# Peripheral.net
KiCad netlist of a schematic drawn in Altium Designer
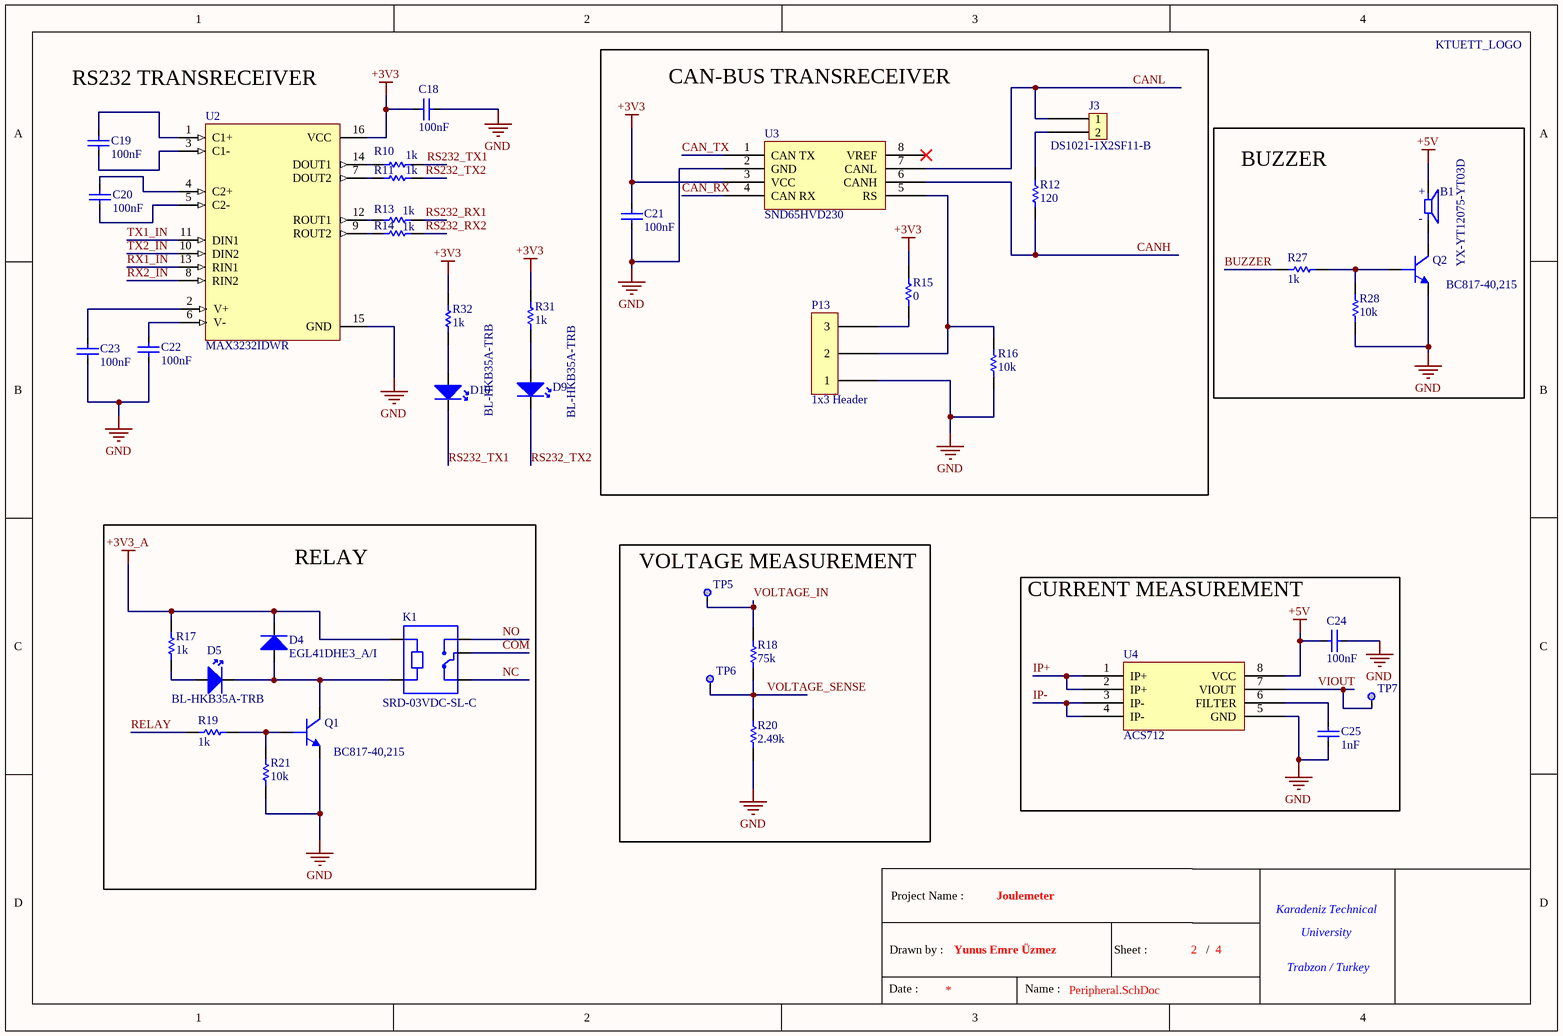
[diagram p0: Peripheral.SchDoc]

(export (version "E")
  (design (tool "Eeschema 10.0.6"))
  (components
    (comp (ref "1")
      (value "KTUETT_LOGO")
      (footprint "KTUETT_LOGO")
      (libsource (lib "Motor_Driver") (part "KTUETT_LOGO"))
    )
    (comp (ref "B1")
      (value "YX-YT12075-YT03D")
      (footprint "BUZZER")
      (fields (field (name "VOLTAGE") "3V") (field (name "MANUFACTURER") "YXDZ"))
      (libsource (lib "jl_lib") (part "YX-YT12075-YT03D"))
    )
    (comp (ref "C18")
      (value "100nF")
      (footprint "CAP-0603")
      (fields
        (field (name "MANUFACTURER") "TDK")
        (field (name "VOLTAGE") "50V")
        (field (name "TOLERANCE") "%10")
      )
      (libsource (lib "Motor_Driver") (part "CGA3E2X7R1H104K080AA"))
    )
    (comp (ref "C19")
      (value "100nF")
      (footprint "CAP-0603")
      (fields
        (field (name "MANUFACTURER") "TDK")
        (field (name "VOLTAGE") "50V")
        (field (name "TOLERANCE") "%10")
      )
      (libsource (lib "Motor_Driver") (part "CGA3E2X7R1H104K080AA"))
    )
    (comp (ref "C20")
      (value "100nF")
      (footprint "CAP-0603")
      (fields
        (field (name "MANUFACTURER") "TDK")
        (field (name "VOLTAGE") "50V")
        (field (name "TOLERANCE") "%10")
      )
      (libsource (lib "Motor_Driver") (part "CGA3E2X7R1H104K080AA"))
    )
    (comp (ref "C21")
      (value "100nF")
      (footprint "CAP-0603")
      (fields
        (field (name "MANUFACTURER") "TDK")
        (field (name "VOLTAGE") "50V")
        (field (name "TOLERANCE") "%10")
      )
      (libsource (lib "Motor_Driver") (part "CGA3E2X7R1H104K080AA"))
    )
    (comp (ref "C22")
      (value "100nF")
      (footprint "CAP-0603")
      (fields
        (field (name "MANUFACTURER") "TDK")
        (field (name "VOLTAGE") "50V")
        (field (name "TOLERANCE") "%10")
      )
      (libsource (lib "Motor_Driver") (part "CGA3E2X7R1H104K080AA"))
    )
    (comp (ref "C23")
      (value "100nF")
      (footprint "CAP-0603")
      (fields
        (field (name "MANUFACTURER") "TDK")
        (field (name "VOLTAGE") "50V")
        (field (name "TOLERANCE") "%10")
      )
      (libsource (lib "Motor_Driver") (part "CGA3E2X7R1H104K080AA"))
    )
    (comp (ref "C24")
      (value "100nF")
      (footprint "CAP-0603")
      (fields
        (field (name "MANUFACTURER") "TDK")
        (field (name "VOLTAGE") "50V")
        (field (name "TOLERANCE") "%10")
      )
      (libsource (lib "Motor_Driver") (part "CGA3E2X7R1H104K080AA"))
    )
    (comp (ref "C25")
      (value "1nF")
      (footprint "CAP-0603")
      (fields
        (field (name "MANUFACTURER") "KEMET")
        (field (name "TOLERANCE") "%1")
        (field (name "VOLTAGE") "50V")
      )
      (libsource (lib "jl_lib") (part "C0603C102F5GACTU"))
    )
    (comp (ref "D4")
      (value "EGL41DHE3_A/I")
      (footprint "DO-213AB")
      (fields (field (name "MANUFACTURER") "VISHAY") (field (name "VOLTAGE") "200"))
      (libsource (lib "jl_lib") (part "EGL41DHE3_A/I"))
    )
    (comp (ref "D5")
      (value "BL-HKB35A-TRB")
      (footprint "LED-0805")
      (fields (field (name "MANUFACTURER") "BRIGHT LED"))
      (libsource (lib "Motor_Driver") (part "BL-HKB35A-TRB"))
    )
    (comp (ref "D9")
      (value "BL-HKB35A-TRB")
      (footprint "LED-0805")
      (fields (field (name "MANUFACTURER") "BRIGHT LED"))
      (libsource (lib "Motor_Driver") (part "BL-HKB35A-TRB"))
    )
    (comp (ref "D10")
      (value "BL-HKB35A-TRB")
      (footprint "LED-0805")
      (fields (field (name "MANUFACTURER") "BRIGHT LED"))
      (libsource (lib "Motor_Driver") (part "BL-HKB35A-TRB"))
    )
    (comp (ref "J3")
      (value "DS1021-1X2SF11-B")
      (footprint "1x2 HEADER")
      (fields (field (name "MANUFACTURER") "KLS Electronic"))
      (libsource (lib "jl_lib") (part "DS1021-1X2SF11-B"))
    )
    (comp (ref "K1")
      (value "SRD-03VDC-SL-C")
      (footprint "RELAY")
      (fields (field (name "MANUFACTURER") "Songle"))
      (libsource (lib "jl_lib") (part "SRD-03VDC-SL-C"))
    )
    (comp (ref "P13")
      (value "1x3 Header")
      (footprint "1x3 Header (2.54 mm)")
      (libsource (lib "LoRatoUSB") (part "1x3 Header"))
    )
    (comp (ref "Q1")
      (value "BC817-40,215")
      (footprint "SOT23-3")
      (libsource (lib "Motor_Driver") (part "BC817-40,215"))
    )
    (comp (ref "Q2")
      (value "BC817-40,215")
      (footprint "SOT23-3")
      (libsource (lib "Motor_Driver") (part "BC817-40,215"))
    )
    (comp (ref "R10")
      (value "1k")
      (footprint "Motor_Driver:RES-0603")
      (fields
        (field (name "MANUFACTURER") "Vishay")
        (field (name "TOLERANCE") "%1")
        (field (name "POWER") "0.1W")
      )
      (libsource (lib "My_Libs") (part "CRCW06031K00FKEAC"))
    )
    (comp (ref "R11")
      (value "1k")
      (footprint "Motor_Driver:RES-0603")
      (fields
        (field (name "MANUFACTURER") "Vishay")
        (field (name "TOLERANCE") "%1")
        (field (name "POWER") "0.1W")
      )
      (libsource (lib "My_Libs") (part "CRCW06031K00FKEAC"))
    )
    (comp (ref "R12")
      (value "120")
      (footprint "RES-0603")
      (fields
        (field (name "MANUFACTURER") "YAGEO")
        (field (name "TOLERANCE") "%1")
        (field (name "VOLTAGE") "75V")
      )
      (libsource (lib "jl_lib") (part "RC0603FR-07120RL"))
    )
    (comp (ref "R13")
      (value "1k")
      (footprint "Motor_Driver:RES-0603")
      (fields
        (field (name "MANUFACTURER") "Vishay")
        (field (name "TOLERANCE") "%1")
        (field (name "POWER") "0.1W")
      )
      (libsource (lib "My_Libs") (part "CRCW06031K00FKEAC"))
    )
    (comp (ref "R14")
      (value "1k")
      (footprint "Motor_Driver:RES-0603")
      (fields
        (field (name "MANUFACTURER") "Vishay")
        (field (name "TOLERANCE") "%1")
        (field (name "POWER") "0.1W")
      )
      (libsource (lib "My_Libs") (part "CRCW06031K00FKEAC"))
    )
    (comp (ref "R15")
      (value "0")
      (footprint "RES-0603")
      (fields
        (field (name "TOLERANCE") "%5")
        (field (name "MANUFACTURER") "ROYALOHM")
        (field (name "VOLTAGE") "75V")
      )
      (libsource (lib "jl_lib") (part "0603SAJ0000T5E"))
    )
    (comp (ref "R16")
      (value "10k")
      (footprint "Motor_Driver:RES-0603")
      (fields
        (field (name "MANUFACTURER") "Vishay")
        (field (name "TOLERANCE") "%1")
        (field (name "POWER") "0.1W")
      )
      (libsource (lib "My_Libs") (part "CRCW060310K0FKEA"))
    )
    (comp (ref "R17")
      (value "1k")
      (footprint "Motor_Driver:RES-0603")
      (fields
        (field (name "MANUFACTURER") "Vishay")
        (field (name "TOLERANCE") "%1")
        (field (name "POWER") "0.1W")
      )
      (libsource (lib "My_Libs") (part "CRCW06031K00FKEAC"))
    )
    (comp (ref "R18")
      (value "75k")
      (footprint "Motor_Driver:RES-0603")
      (fields
        (field (name "MANUFACTURER") "Panasonic")
        (field (name "TOLERANCE") "%1")
        (field (name "POWER") "0.1W")
      )
      (libsource (lib "My_Libs") (part "ERJ-3EKF7502V"))
    )
    (comp (ref "R19")
      (value "1k")
      (footprint "Motor_Driver:RES-0603")
      (fields
        (field (name "MANUFACTURER") "Vishay")
        (field (name "TOLERANCE") "%1")
        (field (name "POWER") "0.1W")
      )
      (libsource (lib "My_Libs") (part "CRCW06031K00FKEAC"))
    )
    (comp (ref "R20")
      (value "2.49k")
      (footprint "Motor_Driver:RES-0603")
      (fields
        (field (name "MANUFACTURER") "Vishay")
        (field (name "TOLERANCE") "%1")
        (field (name "POWER") "0.1W")
      )
      (libsource (lib "My_Libs") (part "CRCW06032K49FKEB"))
    )
    (comp (ref "R21")
      (value "10k")
      (footprint "Motor_Driver:RES-0603")
      (fields
        (field (name "MANUFACTURER") "Vishay")
        (field (name "TOLERANCE") "%1")
        (field (name "POWER") "0.1W")
      )
      (libsource (lib "My_Libs") (part "CRCW060310K0FKEA"))
    )
    (comp (ref "R27")
      (value "1k")
      (footprint "Motor_Driver:RES-0603")
      (fields
        (field (name "MANUFACTURER") "Vishay")
        (field (name "TOLERANCE") "%1")
        (field (name "POWER") "0.1W")
      )
      (libsource (lib "My_Libs") (part "CRCW06031K00FKEAC"))
    )
    (comp (ref "R28")
      (value "10k")
      (footprint "Motor_Driver:RES-0603")
      (fields
        (field (name "MANUFACTURER") "Vishay")
        (field (name "TOLERANCE") "%1")
        (field (name "POWER") "0.1W")
      )
      (libsource (lib "My_Libs") (part "CRCW060310K0FKEA"))
    )
    (comp (ref "R31")
      (value "1k")
      (footprint "RES-0603")
      (fields
        (field (name "MANUFACTURER") "Vishay")
        (field (name "TOLERANCE") "%1")
        (field (name "POWER") "0.1W")
      )
      (libsource (lib "Motor_Driver") (part "CRCW06031K00FKEAC"))
    )
    (comp (ref "R32")
      (value "1k")
      (footprint "RES-0603")
      (fields
        (field (name "MANUFACTURER") "Vishay")
        (field (name "TOLERANCE") "%1")
        (field (name "POWER") "0.1W")
      )
      (libsource (lib "Motor_Driver") (part "CRCW06031K00FKEAC"))
    )
    (comp (ref "TP5")
      (value "Test Point")
      (footprint "0.8mm Test Point")
      (libsource (lib "Motor_Driver") (part "Test Point"))
    )
    (comp (ref "TP6")
      (value "Test Point")
      (footprint "0.8mm Test Point")
      (libsource (lib "Motor_Driver") (part "Test Point"))
    )
    (comp (ref "TP7")
      (value "Test Point")
      (footprint "0.8mm Test Point")
      (libsource (lib "Motor_Driver") (part "Test Point"))
    )
    (comp (ref "U2")
      (value "MAX3232IDWR")
      (footprint "SOIC-16")
      (fields (field (name "MANUFACTURER") "Texas"))
      (libsource (lib "jl_lib") (part "MAX3232IDWR"))
    )
    (comp (ref "U3")
      (value "SND65HVD230")
      (footprint "SOIC-8")
      (fields (field (name "MANUFACTURER") "TI"))
      (libsource (lib "jl_lib") (part "SND65HVD230"))
    )
    (comp (ref "U4")
      (value "ACS712")
      (footprint "SOIC-8")
      (fields (field (name "MANUFACTURER") "Allegro"))
      (libsource (lib "jl_lib") (part "ACS712"))
    )
  )
  (nets
    (net (code "1") (name "+3V3") (class "Default")
      (node (ref "C18") (pin "2") (pinfunction "2_2") (pintype "passive"))
      (node (ref "C21") (pin "1") (pinfunction "1_1") (pintype "passive"))
      (node (ref "R15") (pin "2") (pinfunction "2_2") (pintype "passive"))
      (node (ref "R31") (pin "2") (pinfunction "2_2") (pintype "passive"))
      (node (ref "R32") (pin "2") (pinfunction "2_2") (pintype "passive"))
      (node (ref "U2") (pin "16") (pinfunction "VCC_16") (pintype "power_in"))
      (node (ref "U3") (pin "3") (pinfunction "VCC_3") (pintype "passive"))
    )
    (net (code "2") (name "+3V3_A") (class "Default")
      (node (ref "D4") (pin "2") (pinfunction "K_2") (pintype "passive"))
      (node (ref "K1") (pin "A1") (pinfunction "A1_A1") (pintype "passive"))
      (node (ref "R17") (pin "1") (pinfunction "1_1") (pintype "passive"))
    )
    (net (code "3") (name "+5V") (class "Default")
      (node (ref "B1") (pin "P") (pinfunction "P_P") (pintype "passive"))
      (node (ref "C24") (pin "1") (pinfunction "1_1") (pintype "passive"))
      (node (ref "U4") (pin "8") (pinfunction "VCC_8") (pintype "passive"))
    )
    (net (code "4") (name "/BUZZER") (class "Default")
      (node (ref "R27") (pin "2") (pinfunction "2_2") (pintype "passive"))
    )
    (net (code "5") (name "/CANH") (class "Default")
      (node (ref "R12") (pin "2") (pinfunction "2_2") (pintype "passive"))
      (node (ref "U3") (pin "6") (pinfunction "CANH_6") (pintype "passive"))
    )
    (net (code "6") (name "/CANL") (class "Default")
      (node (ref "J3") (pin "1") (pinfunction "1_1") (pintype "passive"))
      (node (ref "U3") (pin "7") (pinfunction "CANL_7") (pintype "passive"))
    )
    (net (code "7") (name "/CAN_RX") (class "Default")
      (node (ref "U3") (pin "4") (pinfunction "CAN_RX_4") (pintype "passive"))
    )
    (net (code "8") (name "/CAN_TX") (class "Default")
      (node (ref "U3") (pin "1") (pinfunction "CAN_TX_1") (pintype "passive"))
    )
    (net (code "9") (name "/COM") (class "Default")
      (node (ref "K1") (pin "COM") (pinfunction "COM_COM") (pintype "passive"))
    )
    (net (code "10") (name "/IP+") (class "Default")
      (node (ref "U4") (pin "1") (pinfunction "IP+_1") (pintype "passive"))
      (node (ref "U4") (pin "2") (pinfunction "IP+_2") (pintype "passive"))
    )
    (net (code "11") (name "/IP-") (class "Default")
      (node (ref "U4") (pin "3") (pinfunction "IP-_3") (pintype "passive"))
      (node (ref "U4") (pin "4") (pinfunction "IP-_4") (pintype "passive"))
    )
    (net (code "12") (name "/NC") (class "Default")
      (node (ref "K1") (pin "NC") (pinfunction "NC_NC") (pintype "passive"))
    )
    (net (code "13") (name "/NO") (class "Default")
      (node (ref "K1") (pin "NO") (pinfunction "NO_NO") (pintype "passive"))
    )
    (net (code "14") (name "/RELAY") (class "Default")
      (node (ref "R19") (pin "2") (pinfunction "2_2") (pintype "passive"))
    )
    (net (code "15") (name "/RS232_RX1") (class "Default")
      (node (ref "R13") (pin "1") (pinfunction "1_1") (pintype "passive"))
    )
    (net (code "16") (name "/RS232_RX2") (class "Default")
      (node (ref "R14") (pin "1") (pinfunction "1_1") (pintype "passive"))
    )
    (net (code "17") (name "/RS232_TX1") (class "Default")
      (node (ref "D10") (pin "2") (pinfunction "K_2") (pintype "passive"))
      (node (ref "R10") (pin "1") (pinfunction "1_1") (pintype "passive"))
    )
    (net (code "18") (name "/RS232_TX2") (class "Default")
      (node (ref "D9") (pin "2") (pinfunction "K_2") (pintype "passive"))
      (node (ref "R11") (pin "1") (pinfunction "1_1") (pintype "passive"))
    )
    (net (code "19") (name "/RX1_IN") (class "Default")
      (node (ref "U2") (pin "13") (pinfunction "RIN1_13") (pintype "input"))
    )
    (net (code "20") (name "/RX2_IN") (class "Default")
      (node (ref "U2") (pin "8") (pinfunction "RIN2_8") (pintype "input"))
    )
    (net (code "21") (name "/TX1_IN") (class "Default")
      (node (ref "U2") (pin "11") (pinfunction "DIN1_11") (pintype "input"))
    )
    (net (code "22") (name "/TX2_IN") (class "Default")
      (node (ref "U2") (pin "10") (pinfunction "DIN2_10") (pintype "input"))
    )
    (net (code "23") (name "/VIOUT") (class "Default")
      (node (ref "TP7") (pin "1") (pinfunction "1_1") (pintype "passive"))
      (node (ref "U4") (pin "7") (pinfunction "VIOUT_7") (pintype "passive"))
    )
    (net (code "24") (name "/VOLTAGE_IN") (class "Default")
      (node (ref "R18") (pin "1") (pinfunction "1_1") (pintype "passive"))
      (node (ref "TP5") (pin "1") (pinfunction "1_1") (pintype "passive"))
    )
    (net (code "25") (name "/VOLTAGE_SENSE") (class "Default")
      (node (ref "R18") (pin "2") (pinfunction "2_2") (pintype "passive"))
      (node (ref "R20") (pin "2") (pinfunction "2_2") (pintype "passive"))
      (node (ref "TP6") (pin "1") (pinfunction "1_1") (pintype "passive"))
    )
    (net (code "26") (name "GND") (class "Default")
      (node (ref "C18") (pin "1") (pinfunction "1_1") (pintype "passive"))
      (node (ref "C21") (pin "2") (pinfunction "2_2") (pintype "passive"))
      (node (ref "C22") (pin "2") (pinfunction "2_2") (pintype "passive"))
      (node (ref "C23") (pin "2") (pinfunction "2_2") (pintype "passive"))
      (node (ref "C24") (pin "2") (pinfunction "2_2") (pintype "passive"))
      (node (ref "C25") (pin "1") (pinfunction "1_1") (pintype "passive"))
      (node (ref "P13") (pin "1") (pinfunction "1_1") (pintype "passive"))
      (node (ref "Q1") (pin "2") (pinfunction "E_2") (pintype "passive"))
      (node (ref "Q2") (pin "2") (pinfunction "E_2") (pintype "passive"))
      (node (ref "R16") (pin "1") (pinfunction "1_1") (pintype "passive"))
      (node (ref "R20") (pin "1") (pinfunction "1_1") (pintype "passive"))
      (node (ref "R21") (pin "1") (pinfunction "1_1") (pintype "passive"))
      (node (ref "R28") (pin "1") (pinfunction "1_1") (pintype "passive"))
      (node (ref "U2") (pin "15") (pinfunction "GND_15") (pintype "power_in"))
      (node (ref "U3") (pin "2") (pinfunction "GND_2") (pintype "passive"))
      (node (ref "U4") (pin "5") (pinfunction "GND_5") (pintype "passive"))
    )
    (net (code "27") (name "Net-(D4-A)") (class "Default")
      (node (ref "D4") (pin "1") (pinfunction "A_1") (pintype "passive"))
      (node (ref "D5") (pin "2") (pinfunction "K_2") (pintype "passive"))
      (node (ref "K1") (pin "A2") (pinfunction "A2_A2") (pintype "passive"))
      (node (ref "Q1") (pin "3") (pinfunction "C_3") (pintype "passive"))
    )
    (net (code "28") (name "Net-(D5-A)") (class "Default")
      (node (ref "D5") (pin "1") (pinfunction "A_1") (pintype "passive"))
      (node (ref "R17") (pin "2") (pinfunction "2_2") (pintype "passive"))
    )
    (net (code "29") (name "Net-(D9-A)") (class "Default")
      (node (ref "D9") (pin "1") (pinfunction "A_1") (pintype "passive"))
      (node (ref "R31") (pin "1") (pinfunction "1_1") (pintype "passive"))
    )
    (net (code "30") (name "Net-(D10-A)") (class "Default")
      (node (ref "D10") (pin "1") (pinfunction "A_1") (pintype "passive"))
      (node (ref "R32") (pin "1") (pinfunction "1_1") (pintype "passive"))
    )
    (net (code "31") (name "Net-(J3-Pad2)") (class "Default")
      (node (ref "J3") (pin "2") (pinfunction "2_2") (pintype "passive"))
      (node (ref "R12") (pin "1") (pinfunction "1_1") (pintype "passive"))
    )
    (net (code "32") (name "Net-(P13-Pad3)") (class "Default")
      (node (ref "P13") (pin "3") (pinfunction "3_3") (pintype "passive"))
      (node (ref "R15") (pin "1") (pinfunction "1_1") (pintype "passive"))
    )
    (net (code "33") (name "Net-(Q1-B)") (class "Default")
      (node (ref "Q1") (pin "1") (pinfunction "B_1") (pintype "passive"))
      (node (ref "R19") (pin "1") (pinfunction "1_1") (pintype "passive"))
      (node (ref "R21") (pin "2") (pinfunction "2_2") (pintype "passive"))
    )
    (net (code "34") (name "Net-(Q2-B)") (class "Default")
      (node (ref "Q2") (pin "1") (pinfunction "B_1") (pintype "passive"))
      (node (ref "R27") (pin "1") (pinfunction "1_1") (pintype "passive"))
      (node (ref "R28") (pin "2") (pinfunction "2_2") (pintype "passive"))
    )
    (net (code "35") (name "Net-(Q2-C)") (class "Default")
      (node (ref "B1") (pin "N") (pinfunction "N_N") (pintype "passive"))
      (node (ref "Q2") (pin "3") (pinfunction "C_3") (pintype "passive"))
    )
    (net (code "36") (name "Net-(U2-C1+)") (class "Default")
      (node (ref "C19") (pin "1") (pinfunction "1_1") (pintype "passive"))
      (node (ref "U2") (pin "1") (pinfunction "C1+_1") (pintype "input"))
    )
    (net (code "37") (name "Net-(U2-C1-)") (class "Default")
      (node (ref "C19") (pin "2") (pinfunction "2_2") (pintype "passive"))
      (node (ref "U2") (pin "3") (pinfunction "C1-_3") (pintype "input"))
    )
    (net (code "38") (name "Net-(U2-C2+)") (class "Default")
      (node (ref "C20") (pin "1") (pinfunction "1_1") (pintype "passive"))
      (node (ref "U2") (pin "4") (pinfunction "C2+_4") (pintype "input"))
    )
    (net (code "39") (name "Net-(U2-C2-)") (class "Default")
      (node (ref "C20") (pin "2") (pinfunction "2_2") (pintype "passive"))
      (node (ref "U2") (pin "5") (pinfunction "C2-_5") (pintype "input"))
    )
    (net (code "40") (name "Net-(U2-DOUT1)") (class "Default")
      (node (ref "R10") (pin "2") (pinfunction "2_2") (pintype "passive"))
      (node (ref "U2") (pin "14") (pinfunction "DOUT1_14") (pintype "output"))
    )
    (net (code "41") (name "Net-(U2-DOUT2)") (class "Default")
      (node (ref "R11") (pin "2") (pinfunction "2_2") (pintype "passive"))
      (node (ref "U2") (pin "7") (pinfunction "DOUT2_7") (pintype "output"))
    )
    (net (code "42") (name "Net-(U2-ROUT1)") (class "Default")
      (node (ref "R13") (pin "2") (pinfunction "2_2") (pintype "passive"))
      (node (ref "U2") (pin "12") (pinfunction "ROUT1_12") (pintype "output"))
    )
    (net (code "43") (name "Net-(U2-ROUT2)") (class "Default")
      (node (ref "R14") (pin "2") (pinfunction "2_2") (pintype "passive"))
      (node (ref "U2") (pin "9") (pinfunction "ROUT2_9") (pintype "output"))
    )
    (net (code "44") (name "Net-(U2-V+)") (class "Default")
      (node (ref "C23") (pin "1") (pinfunction "1_1") (pintype "passive"))
      (node (ref "U2") (pin "2") (pinfunction "V+_2") (pintype "input"))
    )
    (net (code "45") (name "Net-(U2-V-)") (class "Default")
      (node (ref "C22") (pin "1") (pinfunction "1_1") (pintype "passive"))
      (node (ref "U2") (pin "6") (pinfunction "V-_6") (pintype "input"))
    )
    (net (code "46") (name "Net-(U3-RS)") (class "Default")
      (node (ref "P13") (pin "2") (pinfunction "2_2") (pintype "passive"))
      (node (ref "R16") (pin "2") (pinfunction "2_2") (pintype "passive"))
      (node (ref "U3") (pin "5") (pinfunction "RS_5") (pintype "passive"))
    )
    (net (code "47") (name "Net-(U4-FILTER)") (class "Default")
      (node (ref "C25") (pin "2") (pinfunction "2_2") (pintype "passive"))
      (node (ref "U4") (pin "6") (pinfunction "FILTER_6") (pintype "passive"))
    )
    (net (code "48") (name "unconnected-(U3-VREF-Pad8)") (class "Default")
      (node (ref "U3") (pin "8") (pinfunction "VREF_8") (pintype "passive+no_connect"))
    )
  )
)
